# USB_AND_POWER.net
KiCad netlist of a schematic drawn in Altium Designer
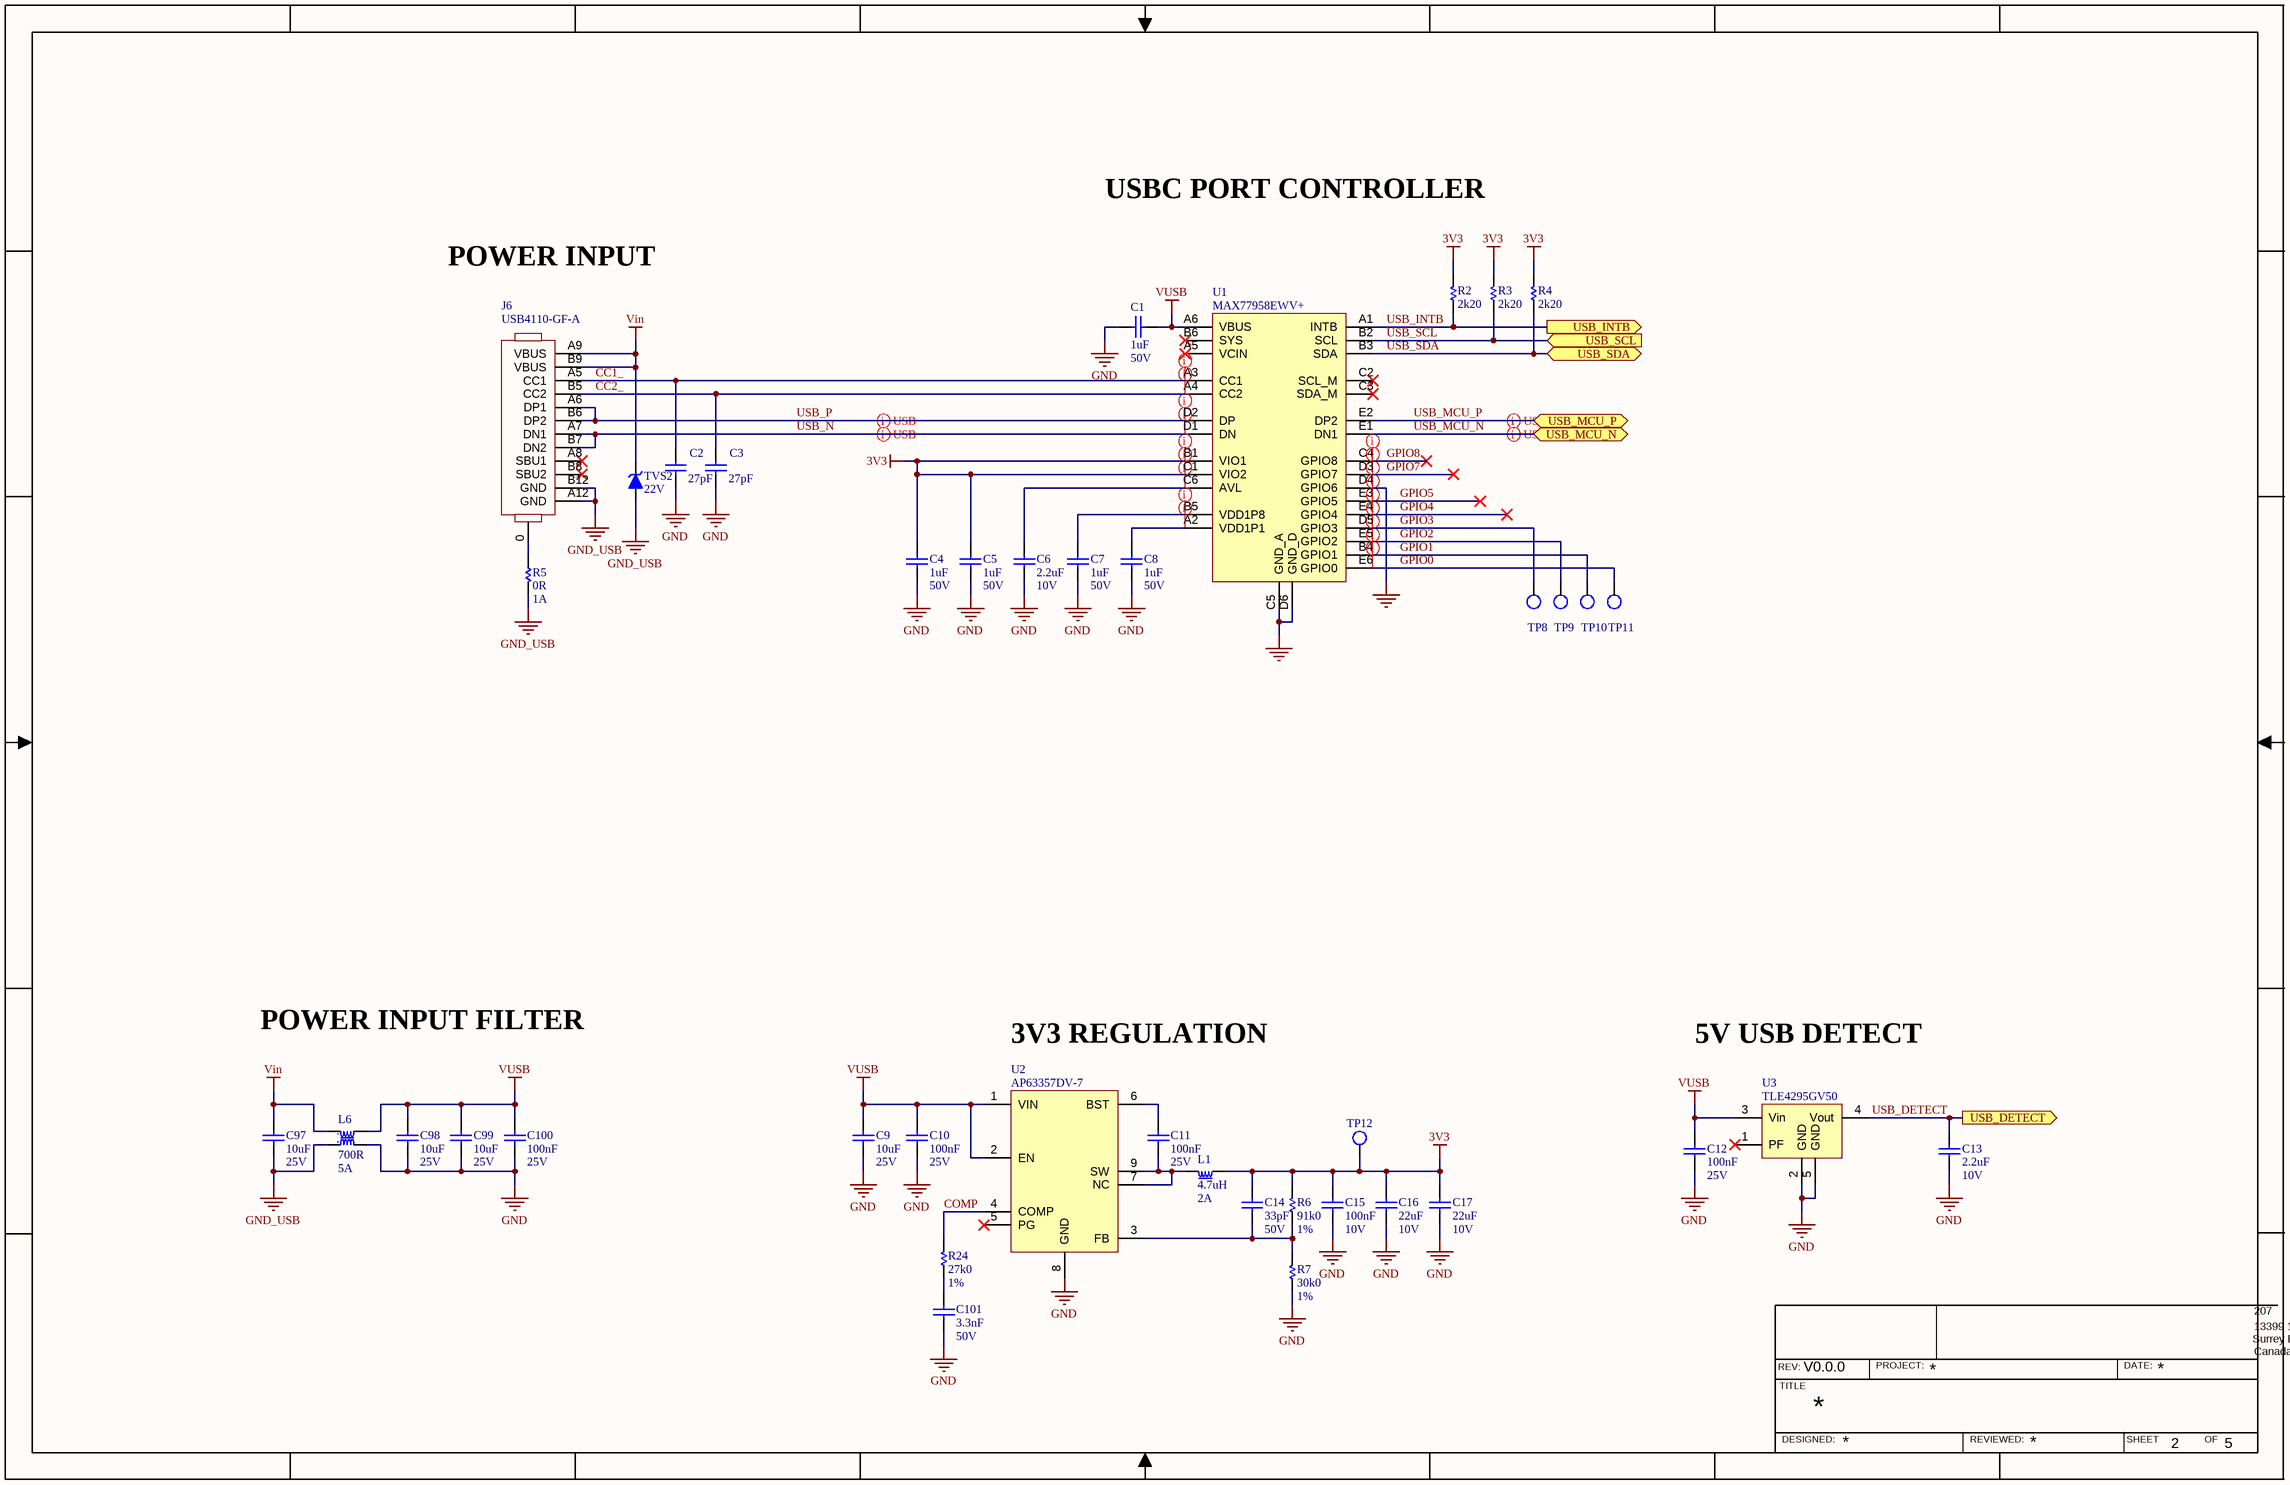
[diagram p0: USB_AND_POWER.SchDoc]

(export (version "E")
  (design (tool "Eeschema 10.0.6"))
  (components
    (comp (ref "C1")
      (value "1uF")
      (footprint "c0603")
      (description "Multilayer Ceramic Capacitors (High dielectric type), 50V, 1 uF, ± 10 %, 0603, X5R, RoHS")
      (fields
        (field (name "MANUFACTURER") "Taiyo Yuden")
        (field (name "MANUFACTURER PART NUMBER") "UMK107BJ105KA-T")
        (field (name "VOLTAGE RATING") "50V")
      )
      (libsource (lib "DClassAmp_Symbol") (part "CAP CER 1uF 50V X5R 0603"))
    )
    (comp (ref "C2")
      (value "27pF")
      (footprint "C0402")
      (description "贴片陶瓷电容  27pF ±5% 50V C0G(NP0) 0402")
      (fields
        (field (name "MANUFACTURER") "Samsung")
        (field (name "MANUFACTURER PART NUMBER") "CL05C270JB5NNNC")
      )
      (libsource (lib "DClassAmp_Symbol") (part "CAP CER 27pF 50V C0G 0402"))
    )
    (comp (ref "C3")
      (value "27pF")
      (footprint "C0402")
      (description "贴片陶瓷电容  27pF ±5% 50V C0G(NP0) 0402")
      (fields
        (field (name "MANUFACTURER") "Samsung")
        (field (name "MANUFACTURER PART NUMBER") "CL05C270JB5NNNC")
      )
      (libsource (lib "DClassAmp_Symbol") (part "CAP CER 27pF 50V C0G 0402"))
    )
    (comp (ref "C4")
      (value "1uF")
      (footprint "c0603")
      (description "Multilayer Ceramic Capacitors (High dielectric type), 50V, 1 uF, ± 10 %, 0603, X5R, RoHS")
      (fields
        (field (name "MANUFACTURER") "Taiyo Yuden")
        (field (name "MANUFACTURER PART NUMBER") "UMK107BJ105KA-T")
        (field (name "VOLTAGE RATING") "50V")
      )
      (libsource (lib "DClassAmp_Symbol") (part "CAP CER 1uF 50V X5R 0603"))
    )
    (comp (ref "C5")
      (value "1uF")
      (footprint "c0603")
      (description "Multilayer Ceramic Capacitors (High dielectric type), 50V, 1 uF, ± 10 %, 0603, X5R, RoHS")
      (fields
        (field (name "MANUFACTURER") "Taiyo Yuden")
        (field (name "MANUFACTURER PART NUMBER") "UMK107BJ105KA-T")
        (field (name "VOLTAGE RATING") "50V")
      )
      (libsource (lib "DClassAmp_Symbol") (part "CAP CER 1uF 50V X5R 0603"))
    )
    (comp (ref "C6")
      (value "2.2uF")
      (footprint "C0402")
      (fields
        (field (name "MANUFACTURER") "Taiyo Yuden")
        (field (name "MANUFACTURER PART NUMBER") "LMK105BJ225MV-F")
        (field (name "TOLERANCE") "20%")
        (field (name "VOLTAGE RATING") "10V")
      )
      (libsource (lib "DClassAmp_Symbol") (part "CAP CER 2.2uF 10V X5R 0402"))
    )
    (comp (ref "C7")
      (value "1uF")
      (footprint "c0603")
      (description "Multilayer Ceramic Capacitors (High dielectric type), 50V, 1 uF, ± 10 %, 0603, X5R, RoHS")
      (fields
        (field (name "MANUFACTURER") "Taiyo Yuden")
        (field (name "MANUFACTURER PART NUMBER") "UMK107BJ105KA-T")
        (field (name "VOLTAGE RATING") "50V")
      )
      (libsource (lib "DClassAmp_Symbol") (part "CAP CER 1uF 50V X5R 0603"))
    )
    (comp (ref "C8")
      (value "1uF")
      (footprint "c0603")
      (description "Multilayer Ceramic Capacitors (High dielectric type), 50V, 1 uF, ± 10 %, 0603, X5R, RoHS")
      (fields
        (field (name "MANUFACTURER") "Taiyo Yuden")
        (field (name "MANUFACTURER PART NUMBER") "UMK107BJ105KA-T")
        (field (name "VOLTAGE RATING") "50V")
      )
      (libsource (lib "DClassAmp_Symbol") (part "CAP CER 1uF 50V X5R 0603"))
    )
    (comp (ref "C9")
      (value "10uF")
      (footprint "c0805")
      (description "Cap Ceramic 10uF 25V X5R 10% SMD 0805 85°C Embossed T/R")
      (fields
        (field (name "MANUFACTURER") "Samsung")
        (field (name "MANUFACTURER PART NUMBER") "CL21A106KAYNNNE")
        (field (name "VOLTAGE RATING") "25V")
      )
      (libsource (lib "DClassAmp_Symbol") (part "CAP CER 10uF 25V X5R 0805"))
    )
    (comp (ref "C10")
      (value "100nF")
      (footprint "C0402")
      (description "Cap Ceramic 0.1uF 25V X5R 10% Pad SMD 0402 85°C T/R / Multi Layer Ceramic Capacitor (MLCC)")
      (fields
        (field (name "MANUFACTURER") "Samsung")
        (field (name "MANUFACTURER PART NUMBER") "CL05A104KA5NNNC")
        (field (name "VOLTAGE RATING") "25V")
      )
      (libsource (lib "DClassAmp_Symbol") (part "CAP CER 100nF 25V X5R 0402"))
    )
    (comp (ref "C11")
      (value "100nF")
      (footprint "C0402")
      (description "Cap Ceramic 0.1uF 25V X5R 10% Pad SMD 0402 85°C T/R / Multi Layer Ceramic Capacitor (MLCC)")
      (fields
        (field (name "MANUFACTURER") "Samsung")
        (field (name "MANUFACTURER PART NUMBER") "CL05A104KA5NNNC")
        (field (name "VOLTAGE RATING") "25V")
      )
      (libsource (lib "DClassAmp_Symbol") (part "CAP CER 100nF 25V X5R 0402"))
    )
    (comp (ref "C12")
      (value "100nF")
      (footprint "C0402")
      (description "Cap Ceramic 0.1uF 25V X5R 10% Pad SMD 0402 85°C T/R / Multi Layer Ceramic Capacitor (MLCC)")
      (fields
        (field (name "MANUFACTURER") "Samsung")
        (field (name "MANUFACTURER PART NUMBER") "CL05A104KA5NNNC")
        (field (name "VOLTAGE RATING") "25V")
      )
      (libsource (lib "DClassAmp_Symbol") (part "CAP CER 100nF 25V X5R 0402"))
    )
    (comp (ref "C13")
      (value "2.2uF")
      (footprint "C0402")
      (fields
        (field (name "MANUFACTURER") "Taiyo Yuden")
        (field (name "MANUFACTURER PART NUMBER") "LMK105BJ225MV-F")
        (field (name "TOLERANCE") "20%")
        (field (name "VOLTAGE RATING") "10V")
      )
      (libsource (lib "DClassAmp_Symbol") (part "CAP CER 2.2uF 10V X5R 0402"))
    )
    (comp (ref "C14")
      (value "33pF")
      (footprint "C0402")
      (description "0402 33 pF 50 V ±5 % Tolerance NP0 SMT Multilayer Ceramic Capacitor")
      (fields
        (field (name "MANUFACTURER") "Yageo")
        (field (name "MANUFACTURER PART NUMBER") "CC0402JRNPO9BN330")
        (field (name "VOLTAGE RATING (DC)") "50V")
      )
      (libsource (lib "MCU") (part "CAP CER 33pF 50V C0G 0402"))
    )
    (comp (ref "C15")
      (value "100nF")
      (footprint "C0201")
      (description "CAP CER 0.1UF 10V X5R 0201")
      (fields (field (name "TOLERANCE") "20%") (field (name "VOLTAGE RATING") "10V"))
      (libsource (lib "MCU") (part "CAP CER 100nF 10V X5R 0201"))
    )
    (comp (ref "C16")
      (value "22uF")
      (footprint "c0603")
      (description "0603 22 uF 10 V ±20% Tolerance X5R Multilayer Ceramic Chip Capacitor")
      (fields
        (field (name "MANUFACTURER") "Murata")
        (field (name "MANUFACTURER PART NUMBER") "GRM188R61A226ME15D")
        (field (name "VOLTAGE RATING") "10V")
      )
      (libsource (lib "MCU") (part "CAP CER 22uF 10V X5R 0603"))
    )
    (comp (ref "C17")
      (value "22uF")
      (footprint "c0603")
      (description "0603 22 uF 10 V ±20% Tolerance X5R Multilayer Ceramic Chip Capacitor")
      (fields
        (field (name "MANUFACTURER") "Murata")
        (field (name "MANUFACTURER PART NUMBER") "GRM188R61A226ME15D")
        (field (name "VOLTAGE RATING") "10V")
      )
      (libsource (lib "MCU") (part "CAP CER 22uF 10V X5R 0603"))
    )
    (comp (ref "C97")
      (value "10uF")
      (footprint "c0805")
      (description "Cap Ceramic 10uF 25V X5R 10% SMD 0805 85°C Embossed T/R")
      (fields
        (field (name "MANUFACTURER") "Samsung")
        (field (name "MANUFACTURER PART NUMBER") "CL21A106KAYNNNE")
        (field (name "VOLTAGE RATING") "25V")
      )
      (libsource (lib "DClassAmp_Symbol") (part "CAP CER 10uF 25V X5R 0805"))
    )
    (comp (ref "C98")
      (value "10uF")
      (footprint "c0805")
      (description "Cap Ceramic 10uF 25V X5R 10% SMD 0805 85°C Embossed T/R")
      (fields
        (field (name "MANUFACTURER") "Samsung")
        (field (name "MANUFACTURER PART NUMBER") "CL21A106KAYNNNE")
        (field (name "VOLTAGE RATING") "25V")
      )
      (libsource (lib "DClassAmp_Symbol") (part "CAP CER 10uF 25V X5R 0805"))
    )
    (comp (ref "C99")
      (value "10uF")
      (footprint "c0805")
      (description "Cap Ceramic 10uF 25V X5R 10% SMD 0805 85°C Embossed T/R")
      (fields
        (field (name "MANUFACTURER") "Samsung")
        (field (name "MANUFACTURER PART NUMBER") "CL21A106KAYNNNE")
        (field (name "VOLTAGE RATING") "25V")
      )
      (libsource (lib "DClassAmp_Symbol") (part "CAP CER 10uF 25V X5R 0805"))
    )
    (comp (ref "C100")
      (value "100nF")
      (footprint "C0402")
      (description "Cap Ceramic 0.1uF 25V X5R 10% Pad SMD 0402 85°C T/R / Multi Layer Ceramic Capacitor (MLCC)")
      (fields
        (field (name "MANUFACTURER") "Samsung")
        (field (name "MANUFACTURER PART NUMBER") "CL05A104KA5NNNC")
        (field (name "VOLTAGE RATING") "25V")
      )
      (libsource (lib "DClassAmp_Symbol") (part "CAP CER 100nF 25V X5R 0402"))
    )
    (comp (ref "C101")
      (value "3.3nF")
      (footprint "C0402")
      (description "CAP CER 3300PF 50V X7R 0402")
      (fields
        (field (name "TOLERANCE") "10%")
        (field (name "VOLTAGE") "50V")
        (field (name "VOLTAGE RATING") "50V")
      )
      (libsource (lib "MCU") (part "CAP CER 3.3nF 50V X7R 0402"))
    )
    (comp (ref "J6")
      (value "USB4110-GF-A")
      (footprint "CONN USBC 12PIN RA SMD")
      (description "Conn USB Type C RCP 16 POS 0.3mm/0.5mm Solder ST SMD 16 Terminal 1 Port T/R")
      (fields (field (name "MANUFACTURER") "Global Connector Technology"))
      (libsource (lib "DClassAmp_Symbol") (part "CONN USBC 12PIN RA SMD USB4110-GF-A"))
    )
    (comp (ref "L1")
      (value "4.7uH")
      (footprint "IND 4.9x4.9x3.1mm")
      (description "Inductor Power Shielded Wirewound 4.7uH 20% 100KHz Ferrite 2A 0.072Ohm DCR T/R")
      (fields
        (field (name "MANUFACTURER") "Taiyo Yuden")
        (field (name "MANUFACTURER PART NUMBER") "NRS5020T4R7MMGJ")
        (field (name "SATURATION CURRENT") "2A")
      )
      (libsource (lib "MCU") (part "IND 4.7uH 2A 72mR 5020"))
    )
    (comp (ref "L6")
      (value "700R")
      (footprint "IND CM 9070")
      (description "ACM Series 3628 700 Ohm 5 A 10 mOhm DCR 80 V SMT Common Mode Filter")
      (fields (field (name "MAX DC CURRENT") "5A"))
      (libsource (lib "MCU") (part "IND CM 700R 3A ACM9070-701-2PL-TL01"))
    )
    (comp (ref "R2")
      (value "2k20")
      (footprint "R0402")
      (description "贴片电阻 2200Ω ± 1.00% 0.0625W ± 100ppm/℃ 0402")
      (fields
        (field (name "MANUFACTURER") "Yageo")
        (field (name "MANUFACTURER PART NUMBER") "RC0402FR-072K2L")
      )
      (libsource (lib "MCU") (part "RES 2k20 1% 63mW 0402"))
    )
    (comp (ref "R3")
      (value "2k20")
      (footprint "R0402")
      (description "贴片电阻 2200Ω ± 1.00% 0.0625W ± 100ppm/℃ 0402")
      (fields
        (field (name "MANUFACTURER") "Yageo")
        (field (name "MANUFACTURER PART NUMBER") "RC0402FR-072K2L")
      )
      (libsource (lib "MCU") (part "RES 2k20 1% 63mW 0402"))
    )
    (comp (ref "R4")
      (value "2k20")
      (footprint "R0402")
      (description "贴片电阻 2200Ω ± 1.00% 0.0625W ± 100ppm/℃ 0402")
      (fields
        (field (name "MANUFACTURER") "Yageo")
        (field (name "MANUFACTURER PART NUMBER") "RC0402FR-072K2L")
      )
      (libsource (lib "MCU") (part "RES 2k20 1% 63mW 0402"))
    )
    (comp (ref "R5")
      (value "0R")
      (footprint "R0603")
      (description "Res Thkflm 0603 0 Ohm Jumper 1/10W 100Ppm/ C Smd Rohs Compliant: Yes")
      (fields
        (field (name "MANUFACTURER") "Stackpole Electronics")
        (field (name "MANUFACTURER PART NUMBER") "RMCF0603ZT0R00")
        (field (name "CURRENT RATING") "1A")
      )
      (libsource (lib "DClassAmp_Symbol") (part "RES 0R 100mW 0603"))
    )
    (comp (ref "R6")
      (value "91k0")
      (footprint "r0402")
      (description "Res Thick Film 0402 91K Ohm 1% 0.063W(1/16W) }100ppm/? Molded SMD Paper T/R")
      (fields
        (field (name "MANUFACTURER") "Yageo")
        (field (name "MANUFACTURER PART NUMBER") "RC0402FR-0791KL")
        (field (name "TOLERANCE") "1%")
      )
      (libsource (lib "MCU") (part "RES 91k0 1% 63mW 0402"))
    )
    (comp (ref "R7")
      (value "30k0")
      (footprint "r0402")
      (description "Res General Purpose Thick Film 0402 30k Ohm 1% 1/16W ±100ppm/°C Molded Paper T/R")
      (fields
        (field (name "MANUFACTURER") "Yageo")
        (field (name "MANUFACTURER PART NUMBER") "RC0402FR-0730KL")
        (field (name "TOLERANCE") "1%")
      )
      (libsource (lib "DClassAmp_Symbol") (part "RES 30k0 1% 63mW 0402"))
    )
    (comp (ref "R24")
      (value "27k0")
      (footprint "R0402")
      (description "Res Thick Film 0402 27K Ohm 1% 0.063W(1/16W) ±100ppm/C Pad SMD T/R")
      (fields (field (name "TOLERANCE") "1%"))
      (libsource (lib "MCU") (part "RES 27k0 1% 63mW 0402"))
    )
    (comp (ref "TP8")
      (value "1mm")
      (footprint "TESTPOINT_SMT")
      (description "SMT testpoint")
      (libsource (lib "DClassAmp_Symbol") (part "TP 1mm"))
    )
    (comp (ref "TP9")
      (value "1mm")
      (footprint "TESTPOINT_SMT")
      (description "SMT testpoint")
      (libsource (lib "DClassAmp_Symbol") (part "TP 1mm"))
    )
    (comp (ref "TP10")
      (value "1mm")
      (footprint "TESTPOINT_SMT")
      (description "SMT testpoint")
      (libsource (lib "DClassAmp_Symbol") (part "TP 1mm"))
    )
    (comp (ref "TP11")
      (value "1mm")
      (footprint "TESTPOINT_SMT")
      (description "SMT testpoint")
      (libsource (lib "DClassAmp_Symbol") (part "TP 1mm"))
    )
    (comp (ref "TP12")
      (value "1mm")
      (footprint "TESTPOINT_SMT")
      (description "SMT testpoint")
      (libsource (lib "DClassAmp_Symbol") (part "TP 1mm"))
    )
    (comp (ref "TVS2")
      (value "22V")
      (footprint "DIODE SMA")
      (description "Zen Tvs 400W 22V Uni Do-214Ac Tr13 / Tr Rohs Compliant: Yes")
      (fields
        (field (name "MANUFACTURER") "Littelfuse")
        (field (name "MANUFACTURER PART NUMBER") "SZ1SMA22AT3G")
      )
      (libsource (lib "DClassAmp_Symbol") (part "DIODE TVS 22V SMA"))
    )
    (comp (ref "U1")
      (value "MAX77958EWV+")
      (footprint "BGA30C50P6X5 MAX77958EWV+")
      (description "Industry's Simplest Standalone USB Type-C and USB Power Delivery Controller")
      (fields (field (name "MANUFACTURER") "Maxim"))
      (libsource (lib "DClassAmp_Symbol") (part "IC USBC POWER CONTROLLER STANDALONE MAX77958EWV+"))
    )
    (comp (ref "U2")
      (value "AP63357DV-7")
      (footprint "VDFN3020-13 AP63357DV-7")
      (description "AP63357 Series 32 V 3.5 A 450 kHz Synchronous Buck Converter - DFN3020-13")
      (fields (field (name "MANUFACTURER") "Diodes"))
      (libsource (lib "DClassAmp_Symbol") (part "IC REG BUCK 32V 3.5A AP63357DV-7"))
    )
    (comp (ref "U3")
      (value "TLE4295GV50")
      (footprint "PG-SCT595-5")
      (description "LDO Regulator Pos 5V 0.03A Automotive 5-Pin(3+2Tab) SCT-595")
      (fields (field (name "MANUFACTURER") "Infineon"))
      (libsource (lib "MCU") (part "IC REG LIN 5V 30mA TLE4295GV50"))
    )
  )
  (nets
    (net (code "1") (name "/CC1_") (class "Default")
      (node (ref "C2") (pin "2") (pinfunction "2_2") (pintype "passive"))
      (node (ref "J6") (pin "A5") (pinfunction "CC1_A5") (pintype "passive"))
      (node (ref "U1") (pin "A3") (pinfunction "CC1_A3") (pintype "passive"))
    )
    (net (code "2") (name "/CC2_") (class "Default")
      (node (ref "C3") (pin "2") (pinfunction "2_2") (pintype "passive"))
      (node (ref "J6") (pin "B5") (pinfunction "CC2_B5") (pintype "passive"))
      (node (ref "U1") (pin "A4") (pinfunction "CC2_A4") (pintype "passive"))
    )
    (net (code "3") (name "/COMP") (class "Default")
      (node (ref "R24") (pin "2") (pinfunction "2_2") (pintype "passive"))
      (node (ref "U2") (pin "4") (pinfunction "COMP_4") (pintype "passive"))
    )
    (net (code "4") (name "/GPIO0") (class "Default")
      (node (ref "TP11") (pin "1") (pinfunction "1_1") (pintype "passive"))
      (node (ref "U1") (pin "E6") (pinfunction "GPIO0_E6") (pintype "passive"))
    )
    (net (code "5") (name "/GPIO1") (class "Default")
      (node (ref "TP10") (pin "1") (pinfunction "1_1") (pintype "passive"))
      (node (ref "U1") (pin "B4") (pinfunction "GPIO1_B4") (pintype "passive"))
    )
    (net (code "6") (name "/GPIO2") (class "Default")
      (node (ref "TP9") (pin "1") (pinfunction "1_1") (pintype "passive"))
      (node (ref "U1") (pin "E5") (pinfunction "GPIO2_E5") (pintype "passive"))
    )
    (net (code "7") (name "/GPIO3") (class "Default")
      (node (ref "TP8") (pin "1") (pinfunction "1_1") (pintype "passive"))
      (node (ref "U1") (pin "D5") (pinfunction "GPIO3_D5") (pintype "passive"))
    )
    (net (code "8") (name "/GPIO4") (class "Default")
      (node (ref "U1") (pin "E4") (pinfunction "GPIO4_E4") (pintype "passive+no_connect"))
    )
    (net (code "9") (name "/GPIO5") (class "Default")
      (node (ref "U1") (pin "E3") (pinfunction "GPIO5_E3") (pintype "passive+no_connect"))
    )
    (net (code "10") (name "/GPIO7") (class "Default")
      (node (ref "U1") (pin "D3") (pinfunction "GPIO7_D3") (pintype "passive+no_connect"))
    )
    (net (code "11") (name "/GPIO8") (class "Default")
      (node (ref "U1") (pin "C4") (pinfunction "GPIO8_C4") (pintype "passive+no_connect"))
    )
    (net (code "12") (name "/USB_DETECT") (class "Default")
      (node (ref "C13") (pin "2") (pinfunction "2_2") (pintype "passive"))
      (node (ref "U3") (pin "4") (pinfunction "Vout_4") (pintype "passive"))
    )
    (net (code "13") (name "/USB_INTB") (class "Default")
      (node (ref "R2") (pin "1") (pinfunction "1_1") (pintype "passive"))
      (node (ref "U1") (pin "A1") (pinfunction "INTB_A1") (pintype "passive"))
    )
    (net (code "14") (name "/USB_MCU_N") (class "Default")
      (node (ref "U1") (pin "E1") (pinfunction "DN1_E1") (pintype "passive"))
    )
    (net (code "15") (name "/USB_MCU_P") (class "Default")
      (node (ref "U1") (pin "E2") (pinfunction "DP2_E2") (pintype "passive"))
    )
    (net (code "16") (name "/USB_N") (class "Default")
      (node (ref "J6") (pin "A7") (pinfunction "DN1_A7") (pintype "passive"))
      (node (ref "J6") (pin "B7") (pinfunction "DN2_B7") (pintype "passive"))
      (node (ref "U1") (pin "D1") (pinfunction "DN_D1") (pintype "passive"))
    )
    (net (code "17") (name "/USB_P") (class "Default")
      (node (ref "J6") (pin "A6") (pinfunction "DP1_A6") (pintype "passive"))
      (node (ref "J6") (pin "B6") (pinfunction "DP2_B6") (pintype "passive"))
      (node (ref "U1") (pin "D2") (pinfunction "DP_D2") (pintype "passive"))
    )
    (net (code "18") (name "/USB_SCL") (class "Default")
      (node (ref "R3") (pin "1") (pinfunction "1_1") (pintype "passive"))
      (node (ref "U1") (pin "B2") (pinfunction "SCL_B2") (pintype "passive"))
    )
    (net (code "19") (name "/USB_SDA") (class "Default")
      (node (ref "R4") (pin "1") (pinfunction "1_1") (pintype "passive"))
      (node (ref "U1") (pin "B3") (pinfunction "SDA_B3") (pintype "passive"))
    )
    (net (code "20") (name "3V3") (class "Default")
      (node (ref "C14") (pin "2") (pinfunction "2_2") (pintype "passive"))
      (node (ref "C15") (pin "1") (pinfunction "1_1") (pintype "passive"))
      (node (ref "C16") (pin "2") (pinfunction "2_2") (pintype "passive"))
      (node (ref "C17") (pin "2") (pinfunction "2_2") (pintype "passive"))
      (node (ref "C4") (pin "1") (pinfunction "1_1") (pintype "passive"))
      (node (ref "C5") (pin "1") (pinfunction "1_1") (pintype "passive"))
      (node (ref "L1") (pin "2") (pinfunction "2_2") (pintype "passive"))
      (node (ref "R2") (pin "2") (pinfunction "2_2") (pintype "passive"))
      (node (ref "R3") (pin "2") (pinfunction "2_2") (pintype "passive"))
      (node (ref "R4") (pin "2") (pinfunction "2_2") (pintype "passive"))
      (node (ref "R6") (pin "2") (pinfunction "2_2") (pintype "passive"))
      (node (ref "TP12") (pin "1") (pinfunction "1_1") (pintype "passive"))
      (node (ref "U1") (pin "B1") (pinfunction "VIO1_B1") (pintype "passive"))
      (node (ref "U1") (pin "C1") (pinfunction "VIO2_C1") (pintype "passive"))
    )
    (net (code "21") (name "GND") (class "Default")
      (node (ref "C1") (pin "2") (pinfunction "2_2") (pintype "passive"))
      (node (ref "C10") (pin "2") (pinfunction "2_2") (pintype "passive"))
      (node (ref "C100") (pin "2") (pinfunction "2_2") (pintype "passive"))
      (node (ref "C101") (pin "1") (pinfunction "1_1") (pintype "passive"))
      (node (ref "C12") (pin "2") (pinfunction "2_2") (pintype "passive"))
      (node (ref "C13") (pin "1") (pinfunction "1_1") (pintype "passive"))
      (node (ref "C15") (pin "2") (pinfunction "2_2") (pintype "passive"))
      (node (ref "C16") (pin "1") (pinfunction "1_1") (pintype "passive"))
      (node (ref "C17") (pin "1") (pinfunction "1_1") (pintype "passive"))
      (node (ref "C2") (pin "1") (pinfunction "1_1") (pintype "passive"))
      (node (ref "C3") (pin "1") (pinfunction "1_1") (pintype "passive"))
      (node (ref "C4") (pin "2") (pinfunction "2_2") (pintype "passive"))
      (node (ref "C5") (pin "2") (pinfunction "2_2") (pintype "passive"))
      (node (ref "C6") (pin "1") (pinfunction "1_1") (pintype "passive"))
      (node (ref "C7") (pin "2") (pinfunction "2_2") (pintype "passive"))
      (node (ref "C8") (pin "2") (pinfunction "2_2") (pintype "passive"))
      (node (ref "C9") (pin "1") (pinfunction "1_1") (pintype "passive"))
      (node (ref "C98") (pin "1") (pinfunction "1_1") (pintype "passive"))
      (node (ref "C99") (pin "1") (pinfunction "1_1") (pintype "passive"))
      (node (ref "L6") (pin "3") (pinfunction "3_3") (pintype "passive"))
      (node (ref "R7") (pin "1") (pinfunction "1_1") (pintype "passive"))
      (node (ref "U1") (pin "C5") (pinfunction "GND_A_C5") (pintype "passive"))
      (node (ref "U1") (pin "D4") (pinfunction "GPIO6_D4") (pintype "passive"))
      (node (ref "U1") (pin "D6") (pinfunction "GND_D_D6") (pintype "passive"))
      (node (ref "U2") (pin "8") (pinfunction "GND_8") (pintype "passive"))
      (node (ref "U3") (pin "2") (pinfunction "GND_2") (pintype "passive"))
      (node (ref "U3") (pin "5") (pinfunction "GND_5") (pintype "passive"))
    )
    (net (code "22") (name "GND_USB") (class "Default")
      (node (ref "C97") (pin "1") (pinfunction "1_1") (pintype "passive"))
      (node (ref "J6") (pin "A12") (pinfunction "GND_A12") (pintype "passive"))
      (node (ref "J6") (pin "B12") (pinfunction "GND_B12") (pintype "passive"))
      (node (ref "L6") (pin "4") (pinfunction "4_4") (pintype "passive"))
      (node (ref "R5") (pin "2") (pinfunction "2_2") (pintype "passive"))
      (node (ref "TVS2") (pin "2") (pinfunction "A_2") (pintype "passive"))
    )
    (net (code "23") (name "Net-(C101-Pad2)") (class "Default")
      (node (ref "C101") (pin "2") (pinfunction "2_2") (pintype "passive"))
      (node (ref "R24") (pin "1") (pinfunction "1_1") (pintype "passive"))
    )
    (net (code "24") (name "Net-(J6-Pad0)") (class "Default")
      (node (ref "J6") (pin "0") (pinfunction "0_0") (pintype "passive"))
      (node (ref "R5") (pin "1") (pinfunction "1_1") (pintype "passive"))
    )
    (net (code "25") (name "Net-(U1-AVL)") (class "Default")
      (node (ref "C6") (pin "2") (pinfunction "2_2") (pintype "passive"))
      (node (ref "U1") (pin "C6") (pinfunction "AVL_C6") (pintype "passive"))
    )
    (net (code "26") (name "Net-(U1-VDD1P1)") (class "Default")
      (node (ref "C8") (pin "1") (pinfunction "1_1") (pintype "passive"))
      (node (ref "U1") (pin "A2") (pinfunction "VDD1P1_A2") (pintype "passive"))
    )
    (net (code "27") (name "Net-(U1-VDD1P8)") (class "Default")
      (node (ref "C7") (pin "1") (pinfunction "1_1") (pintype "passive"))
      (node (ref "U1") (pin "B5") (pinfunction "VDD1P8_B5") (pintype "passive"))
    )
    (net (code "28") (name "Net-(U2-BST)") (class "Default")
      (node (ref "C11") (pin "1") (pinfunction "1_1") (pintype "passive"))
      (node (ref "U2") (pin "6") (pinfunction "BST_6") (pintype "passive"))
    )
    (net (code "29") (name "Net-(U2-FB)") (class "Default")
      (node (ref "C14") (pin "1") (pinfunction "1_1") (pintype "passive"))
      (node (ref "R6") (pin "1") (pinfunction "1_1") (pintype "passive"))
      (node (ref "R7") (pin "2") (pinfunction "2_2") (pintype "passive"))
      (node (ref "U2") (pin "3") (pinfunction "FB_3") (pintype "passive"))
    )
    (net (code "30") (name "Net-(U2-NC)") (class "Default")
      (node (ref "C11") (pin "2") (pinfunction "2_2") (pintype "passive"))
      (node (ref "L1") (pin "1") (pinfunction "1_1") (pintype "passive"))
      (node (ref "U2") (pin "7") (pinfunction "NC_7") (pintype "passive"))
      (node (ref "U2") (pin "9") (pinfunction "SW_9") (pintype "passive"))
    )
    (net (code "31") (name "VUSB") (class "Default")
      (node (ref "C1") (pin "1") (pinfunction "1_1") (pintype "passive"))
      (node (ref "C10") (pin "1") (pinfunction "1_1") (pintype "passive"))
      (node (ref "C100") (pin "1") (pinfunction "1_1") (pintype "passive"))
      (node (ref "C12") (pin "1") (pinfunction "1_1") (pintype "passive"))
      (node (ref "C9") (pin "2") (pinfunction "2_2") (pintype "passive"))
      (node (ref "C98") (pin "2") (pinfunction "2_2") (pintype "passive"))
      (node (ref "C99") (pin "2") (pinfunction "2_2") (pintype "passive"))
      (node (ref "L6") (pin "2") (pinfunction "2_2") (pintype "passive"))
      (node (ref "U1") (pin "A6") (pinfunction "VBUS_A6") (pintype "passive"))
      (node (ref "U2") (pin "1") (pinfunction "VIN_1") (pintype "passive"))
      (node (ref "U2") (pin "2") (pinfunction "EN_2") (pintype "passive"))
      (node (ref "U3") (pin "3") (pinfunction "Vin_3") (pintype "passive"))
    )
    (net (code "32") (name "Vin") (class "Default")
      (node (ref "C97") (pin "2") (pinfunction "2_2") (pintype "passive"))
      (node (ref "J6") (pin "A9") (pinfunction "VBUS_A9") (pintype "passive"))
      (node (ref "J6") (pin "B9") (pinfunction "VBUS_B9") (pintype "passive"))
      (node (ref "L6") (pin "1") (pinfunction "1_1") (pintype "passive"))
      (node (ref "TVS2") (pin "1") (pinfunction "K_1") (pintype "passive"))
    )
    (net (code "33") (name "unconnected-(J6-SBU1-PadA8)") (class "Default")
      (node (ref "J6") (pin "A8") (pinfunction "SBU1_A8") (pintype "passive+no_connect"))
    )
    (net (code "34") (name "unconnected-(J6-SBU2-PadB8)") (class "Default")
      (node (ref "J6") (pin "B8") (pinfunction "SBU2_B8") (pintype "passive+no_connect"))
    )
    (net (code "35") (name "unconnected-(U1-SCL_M-PadC2)") (class "Default")
      (node (ref "U1") (pin "C2") (pinfunction "SCL_M_C2") (pintype "passive+no_connect"))
    )
    (net (code "36") (name "unconnected-(U1-SDA_M-PadC3)") (class "Default")
      (node (ref "U1") (pin "C3") (pinfunction "SDA_M_C3") (pintype "passive+no_connect"))
    )
    (net (code "37") (name "unconnected-(U1-SYS-PadB6)") (class "Default")
      (node (ref "U1") (pin "B6") (pinfunction "SYS_B6") (pintype "passive+no_connect"))
    )
    (net (code "38") (name "unconnected-(U1-VCIN-PadA5)") (class "Default")
      (node (ref "U1") (pin "A5") (pinfunction "VCIN_A5") (pintype "passive+no_connect"))
    )
    (net (code "39") (name "unconnected-(U2-PG-Pad5)") (class "Default")
      (node (ref "U2") (pin "5") (pinfunction "PG_5") (pintype "passive+no_connect"))
    )
    (net (code "40") (name "unconnected-(U3-PF-Pad1)") (class "Default")
      (node (ref "U3") (pin "1") (pinfunction "PF_1") (pintype "passive+no_connect"))
    )
  )
)
